# 00-Top-layer.net
KiCad netlist of a schematic drawn in Altium Designer
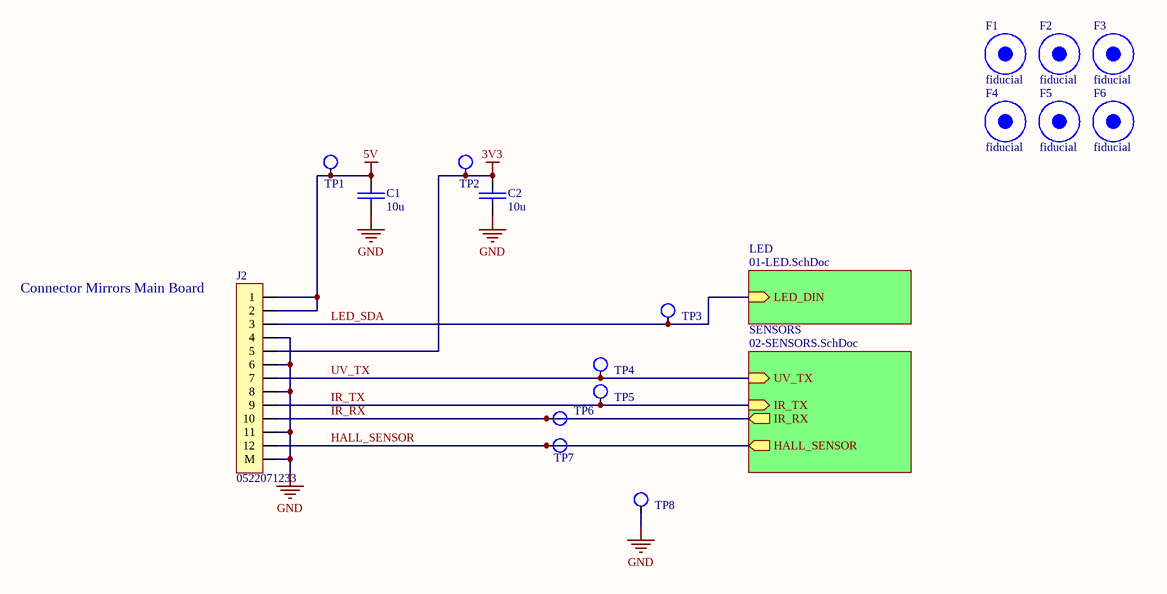
[diagram p0: 00-Top-layer.SchDoc]

(export (version "E")
  (design (tool "Eeschema 10.0.6"))
  (components
    (comp (ref "C1")
      (value "10u")
      (footprint "CAPC100X50X65")
      (description "CAP CER 10UF 10V X5R 0402")
      (fields (field (name "MANUFACTURER") "Samsung Electro-Mechanics"))
      (libsource (lib "FishWand_Schlib") (part "C_10UF_10V_X5R_0402"))
    )
    (comp (ref "C2")
      (value "10u")
      (footprint "CAPC100X50X65")
      (description "CAP CER 10UF 10V X5R 0402")
      (fields (field (name "MANUFACTURER") "Samsung Electro-Mechanics"))
      (libsource (lib "FishWand_Schlib") (part "C_10UF_10V_X5R_0402"))
    )
    (comp (ref "F1")
      (value "fiducial")
      (footprint "fiducial_marker")
      (description "fiducial_marker")
      (libsource (lib "FishWand_Schlib") (part "fiducial_marker"))
    )
    (comp (ref "F2")
      (value "fiducial")
      (footprint "fiducial_marker")
      (description "fiducial_marker")
      (libsource (lib "FishWand_Schlib") (part "fiducial_marker"))
    )
    (comp (ref "F3")
      (value "fiducial")
      (footprint "fiducial_marker")
      (description "fiducial_marker")
      (libsource (lib "FishWand_Schlib") (part "fiducial_marker"))
    )
    (comp (ref "F4")
      (value "fiducial")
      (footprint "fiducial_marker")
      (description "fiducial_marker")
      (libsource (lib "FishWand_Schlib") (part "fiducial_marker"))
    )
    (comp (ref "F5")
      (value "fiducial")
      (footprint "fiducial_marker")
      (description "fiducial_marker")
      (libsource (lib "FishWand_Schlib") (part "fiducial_marker"))
    )
    (comp (ref "F6")
      (value "fiducial")
      (footprint "fiducial_marker")
      (description "fiducial_marker")
      (libsource (lib "FishWand_Schlib") (part "fiducial_marker"))
    )
    (comp (ref "J2")
      (value "0522071233")
      (footprint "CONN_0522711279")
      (description "CONN FPC BOTTOM 12POS 1.00MM R/A")
      (fields (field (name "MANUFACTURER") "Molex"))
      (libsource (lib "FishWand_Schlib") (part "CONN_FPC_Bottom 12POS_1MM_0522711279"))
    )
    (comp (ref "TP1")
      (value "Test Point")
      (footprint "tp_1mm")
      (libsource (lib "FishWand_Schlib") (part "TP_1mm"))
    )
    (comp (ref "TP2")
      (value "Test Point")
      (footprint "tp_1mm")
      (libsource (lib "FishWand_Schlib") (part "TP_1mm"))
    )
    (comp (ref "TP3")
      (value "Test Point")
      (footprint "tp_1mm")
      (libsource (lib "FishWand_Schlib") (part "TP_1mm"))
    )
    (comp (ref "TP4")
      (value "Test Point")
      (footprint "tp_1mm")
      (libsource (lib "FishWand_Schlib") (part "TP_1mm"))
    )
    (comp (ref "TP5")
      (value "Test Point")
      (footprint "tp_1mm")
      (libsource (lib "FishWand_Schlib") (part "TP_1mm"))
    )
    (comp (ref "TP6")
      (value "Test Point")
      (footprint "tp_1mm")
      (libsource (lib "FishWand_Schlib") (part "TP_1mm"))
    )
    (comp (ref "TP7")
      (value "Test Point")
      (footprint "tp_1mm")
      (libsource (lib "FishWand_Schlib") (part "TP_1mm"))
    )
    (comp (ref "TP8")
      (value "Test Point")
      (footprint "tp_1mm")
      (libsource (lib "FishWand_Schlib") (part "TP_1mm"))
    )
  )
  (nets
    (net (code "1") (name "/HALL_SENSOR") (class "Default")
      (node (ref "J2") (pin "12") (pinfunction "12_12") (pintype "passive"))
      (node (ref "TP7") (pin "1") (pinfunction "1_1") (pintype "passive"))
    )
    (net (code "2") (name "/IR_RX") (class "Default")
      (node (ref "J2") (pin "10") (pinfunction "10_10") (pintype "passive"))
      (node (ref "TP6") (pin "1") (pinfunction "1_1") (pintype "passive"))
    )
    (net (code "3") (name "/IR_TX") (class "Default")
      (node (ref "J2") (pin "9") (pinfunction "9_9") (pintype "passive"))
      (node (ref "TP5") (pin "1") (pinfunction "1_1") (pintype "passive"))
    )
    (net (code "4") (name "/LED_SDA") (class "Default")
      (node (ref "J2") (pin "3") (pinfunction "3_3") (pintype "passive"))
      (node (ref "TP3") (pin "1") (pinfunction "1_1") (pintype "passive"))
    )
    (net (code "5") (name "/UV_TX") (class "Default")
      (node (ref "J2") (pin "7") (pinfunction "7_7") (pintype "passive"))
      (node (ref "TP4") (pin "1") (pinfunction "1_1") (pintype "passive"))
    )
    (net (code "6") (name "3V3") (class "Default")
      (node (ref "C2") (pin "1") (pinfunction "1_1") (pintype "passive"))
      (node (ref "J2") (pin "5") (pinfunction "5_5") (pintype "passive"))
      (node (ref "TP2") (pin "1") (pinfunction "1_1") (pintype "passive"))
    )
    (net (code "7") (name "5V") (class "Default")
      (node (ref "C1") (pin "1") (pinfunction "1_1") (pintype "passive"))
      (node (ref "J2") (pin "1") (pinfunction "1_1") (pintype "passive"))
      (node (ref "J2") (pin "2") (pinfunction "2_2") (pintype "passive"))
      (node (ref "TP1") (pin "1") (pinfunction "1_1") (pintype "passive"))
    )
    (net (code "8") (name "GND") (class "Default")
      (node (ref "C1") (pin "2") (pinfunction "2_2") (pintype "passive"))
      (node (ref "C2") (pin "2") (pinfunction "2_2") (pintype "passive"))
      (node (ref "J2") (pin "11") (pinfunction "11_11") (pintype "passive"))
      (node (ref "J2") (pin "4") (pinfunction "4_4") (pintype "passive"))
      (node (ref "J2") (pin "6") (pinfunction "6_6") (pintype "passive"))
      (node (ref "J2") (pin "8") (pinfunction "8_8") (pintype "passive"))
      (node (ref "J2") (pin "M") (pinfunction "M_M") (pintype "passive"))
      (node (ref "TP8") (pin "1") (pinfunction "1_1") (pintype "passive"))
    )
  )
)
